# 3_6_1--esp32_-_7-30_-.net
KiCad netlist of a schematic drawn in EasyEDA Pro
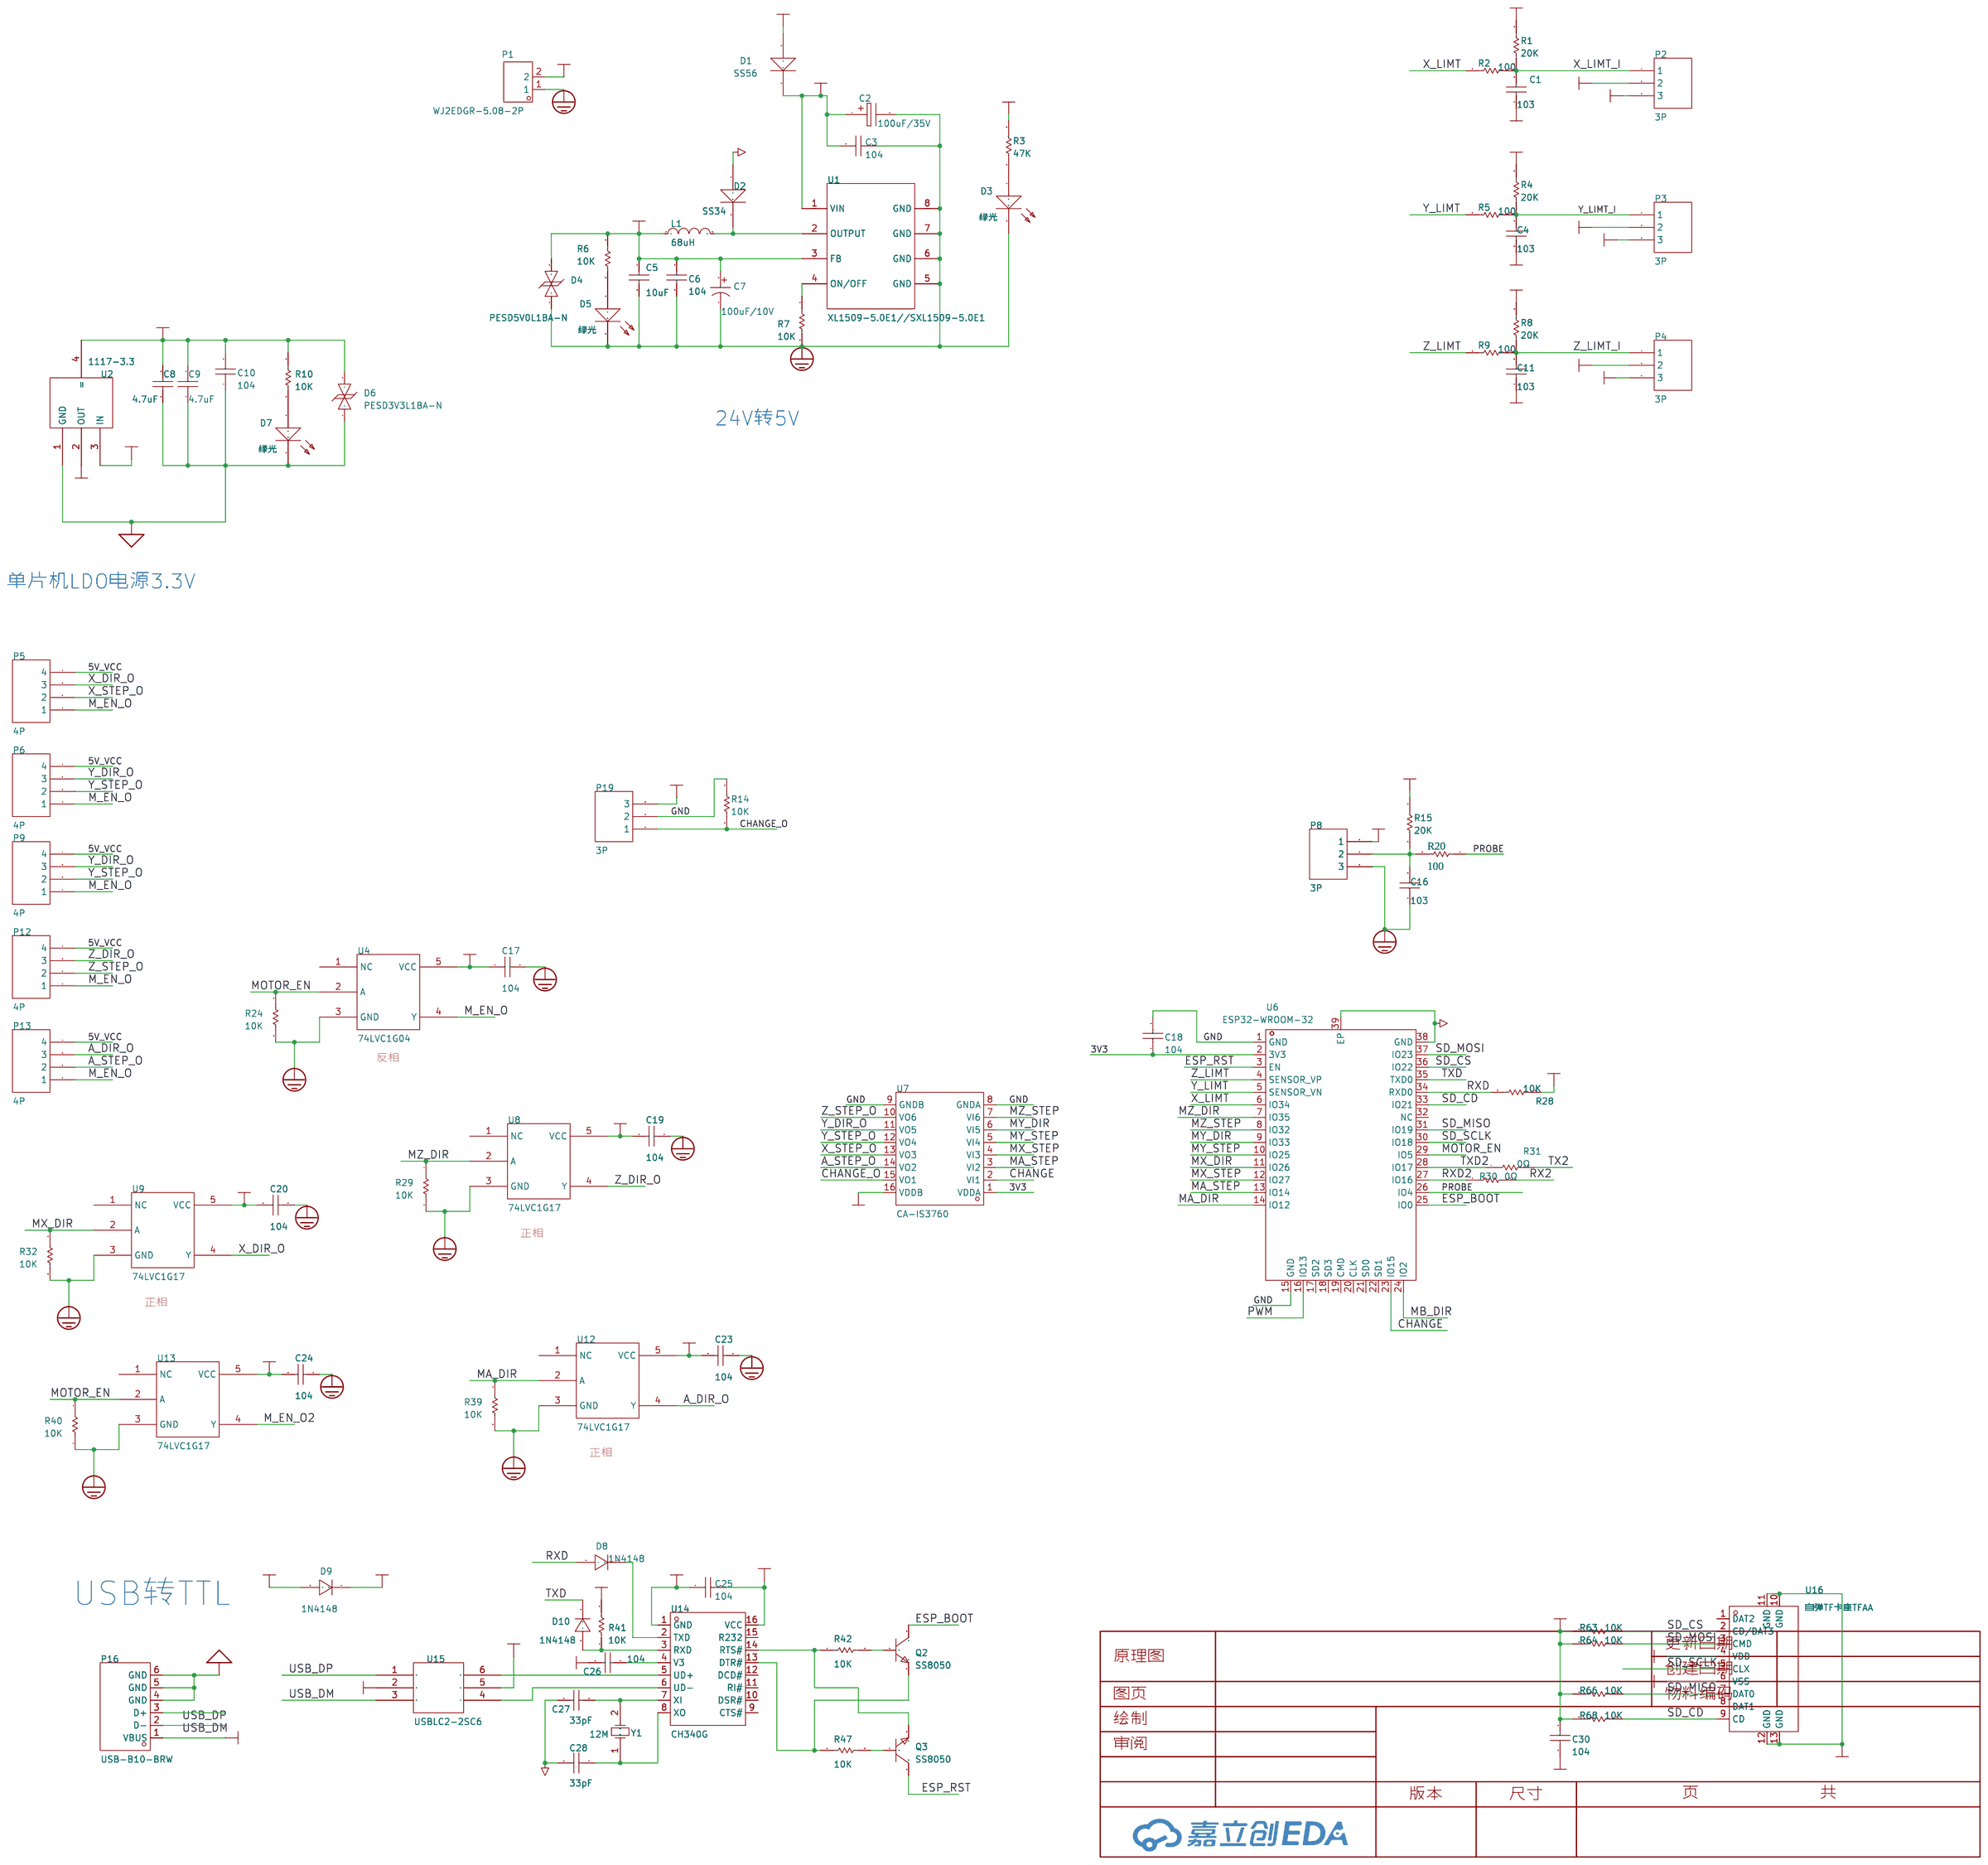
[diagram p0: schematic sheet]

(export (version "E")
  (design (tool "Eeschema 10.0.6"))
  (components
    (comp (ref "C1") (value "103") (footprint "easyedapro:11") (libsource (lib "easyedapro") (part "CAP")))
    (comp (ref "C2")
      (value "100uF/35V")
      (footprint "easyedapro:电解电容贴片10x10")
      (libsource (lib "easyedapro") (part "ELECTRO1"))
    )
    (comp (ref "C3")
      (value "104")
      (footprint "easyedapro:0603C")
      (description "Capacitor (Semiconductor SIM Model)")
      (libsource (lib "easyedapro") (part "Cap Semi"))
    )
    (comp (ref "C4") (value "103") (footprint "easyedapro:11") (libsource (lib "easyedapro") (part "CAP")))
    (comp (ref "C5") (value "10uF") (libsource (lib "") (part "CAP_1")))
    (comp (ref "C6")
      (value "104")
      (footprint "easyedapro:0603C")
      (description "Capacitor (Semiconductor SIM Model)")
      (libsource (lib "easyedapro") (part "Cap Semi"))
    )
    (comp (ref "C7")
      (value "100uF/10V")
      (footprint "easyedapro:CAP-SMD_BD5.0-L5.3-W5.3-RD")
      (fields (field (name "Manufacturer Part") "CS1A101M-CRD54") (field (name "Manufacturer") "ST(先科)"))
      (libsource (lib "easyedapro") (part "CS1A101M-CRD54"))
    )
    (comp (ref "C8") (value "4.7uF") (libsource (lib "") (part "CAP_1")))
    (comp (ref "C9") (value "4.7uF") (libsource (lib "") (part "CAP_1")))
    (comp (ref "C10")
      (value "104")
      (footprint "easyedapro:0603C")
      (description "Capacitor (Semiconductor SIM Model)")
      (libsource (lib "easyedapro") (part "Cap Semi"))
    )
    (comp (ref "C11") (value "103") (footprint "easyedapro:11") (libsource (lib "easyedapro") (part "CAP")))
    (comp (ref "C16") (value "103") (footprint "easyedapro:11") (libsource (lib "easyedapro") (part "CAP")))
    (comp (ref "C17")
      (value "104")
      (footprint "easyedapro:0603C")
      (description "Capacitor (Semiconductor SIM Model)")
      (libsource (lib "easyedapro") (part "Cap Semi"))
    )
    (comp (ref "C18")
      (value "104")
      (footprint "easyedapro:0603C")
      (description "Capacitor (Semiconductor SIM Model)")
      (libsource (lib "easyedapro") (part "Cap Semi"))
    )
    (comp (ref "C19")
      (value "104")
      (footprint "easyedapro:0603C")
      (description "Capacitor (Semiconductor SIM Model)")
      (libsource (lib "easyedapro") (part "Cap Semi"))
    )
    (comp (ref "C20")
      (value "104")
      (footprint "easyedapro:0603C")
      (description "Capacitor (Semiconductor SIM Model)")
      (libsource (lib "easyedapro") (part "Cap Semi"))
    )
    (comp (ref "C23")
      (value "104")
      (footprint "easyedapro:0603C")
      (description "Capacitor (Semiconductor SIM Model)")
      (libsource (lib "easyedapro") (part "Cap Semi"))
    )
    (comp (ref "C24")
      (value "104")
      (footprint "easyedapro:0603C")
      (description "Capacitor (Semiconductor SIM Model)")
      (libsource (lib "easyedapro") (part "Cap Semi"))
    )
    (comp (ref "C25")
      (value "104")
      (footprint "easyedapro:0603C")
      (description "Capacitor (Semiconductor SIM Model)")
      (libsource (lib "easyedapro") (part "Cap Semi"))
    )
    (comp (ref "C26")
      (value "104")
      (footprint "easyedapro:0603C")
      (description "Capacitor (Semiconductor SIM Model)")
      (libsource (lib "easyedapro") (part "Cap Semi"))
    )
    (comp (ref "C27")
      (value "18pF")
      (footprint "easyedapro:0603C")
      (description "Capacitor (Semiconductor SIM Model)")
      (libsource (lib "easyedapro") (part "Cap Semi"))
    )
    (comp (ref "C28")
      (value "18pF")
      (footprint "easyedapro:0603C")
      (description "Capacitor (Semiconductor SIM Model)")
      (libsource (lib "easyedapro") (part "Cap Semi"))
    )
    (comp (ref "C30")
      (value "104")
      (footprint "easyedapro:11")
      (description "Capacitor (Semiconductor SIM Model)")
      (libsource (lib "easyedapro") (part "Cap Semi"))
    )
    (comp (ref "D1") (value "SS56") (footprint "easyedapro:SMA") (libsource (lib "") (part "1N4148_1")))
    (comp (ref "D2") (value "SS34") (libsource (lib "easyedapro") (part "1N4148")))
    (comp (ref "D3")
      (value "绿光")
      (footprint "easyedapro:0603LED")
      (libsource (lib "easyedapro") (part "LED"))
    )
    (comp (ref "D4")
      (value "PESD5V0L1BA-N")
      (footprint "easyedapro:SOD-523_L1.2-W0.8-LS1.6-BI")
      (description "极性:Bidirectional;反向关断电压（典型值）:5V (Max);击穿电压（最小值）:6V;箝位电压:15V;峰值脉冲电流（10/1000us）:5A (8/20us);")
      (fields (field (name "Manufacturer") "BORN伯恩半导体"))
      (libsource (lib "easyedapro") (part "PESD5V0S1BBN"))
    )
    (comp (ref "D5")
      (value "绿光")
      (footprint "easyedapro:0603LED")
      (libsource (lib "easyedapro") (part "LED"))
    )
    (comp (ref "D6")
      (value "PESD3V3L1BA-N")
      (footprint "easyedapro:SOD-523_L1.2-W0.8-LS1.6-BI")
      (description "极性:Bidirectional;反向关断电压（典型值）:5V (Max);击穿电压（最小值）:6V;箝位电压:15V;峰值脉冲电流（10/1000us）:5A (8/20us);")
      (fields (field (name "Manufacturer") "BORN伯恩半导体"))
      (libsource (lib "easyedapro") (part "PESD5V0S1BBN"))
    )
    (comp (ref "D7")
      (value "绿光")
      (footprint "easyedapro:0603LED")
      (libsource (lib "easyedapro") (part "LED"))
    )
    (comp (ref "D8")
      (value "1N4148")
      (footprint "easyedapro:SOD-123_L2.8-W1.8-LS3.7-RD")
      (fields (field (name "Manufacturer") "MCC(美微科)"))
      (libsource (lib "easyedapro") (part "1N4148W-TP"))
    )
    (comp (ref "D9")
      (value "1N4148")
      (footprint "easyedapro:SOD-123_L2.8-W1.8-LS3.7-RD")
      (fields (field (name "Manufacturer") "MCC(美微科)"))
      (libsource (lib "easyedapro") (part "1N4148W-TP"))
    )
    (comp (ref "D10")
      (value "1N4148")
      (footprint "easyedapro:SOD-123_L2.8-W1.8-LS3.7-RD")
      (fields (field (name "Manufacturer") "MCC(美微科)"))
      (libsource (lib "easyedapro") (part "1N4148W-TP"))
    )
    (comp (ref "L1")
      (value "68uH")
      (footprint "easyedapro:IND-SMD_L7.0-W7.0_SMDRI74-330MT")
      (description "电感值:33uH;精度:±20%;额定电流:960mA;饱和电流(Isat):1.8A;类型:屏蔽电感;")
      (fields (field (name "Manufacturer Part") "SMDRI74-330MT") (field (name "Manufacturer") "SXN(顺翔诺)"))
      (libsource (lib "easyedapro") (part "SMDRI74-330MT"))
    )
    (comp (ref "P1")
      (value "WJ2EDGR-5.08-2P")
      (footprint "easyedapro:CONN-TH_WJ2EDGR-5.08-2P")
      (description "每排PIN数:2;安装方式:弯针;排数:1;间距:5.08mm;连接器类型:板端/插座-开口;")
      (fields (field (name "Manufacturer") "KANGNEX(康奈克斯电气)"))
      (libsource (lib "easyedapro") (part "WJ2EDGR-5.08-2P"))
    )
    (comp (ref "P2")
      (value "3P")
      (footprint "easyedapro:HDR1X3_CON")
      (libsource (lib "easyedapro") (part "3P"))
    )
    (comp (ref "P3")
      (value "3P")
      (footprint "easyedapro:HDR1X3_CON")
      (libsource (lib "easyedapro") (part "3P"))
    )
    (comp (ref "P4")
      (value "3P")
      (footprint "easyedapro:HDR1X3_CON")
      (libsource (lib "easyedapro") (part "3P"))
    )
    (comp (ref "P5")
      (value "4P")
      (footprint "easyedapro:HDR1X4_CON")
      (libsource (lib "easyedapro") (part "4P"))
    )
    (comp (ref "P6")
      (value "4P")
      (footprint "easyedapro:HDR1X4_CON")
      (libsource (lib "easyedapro") (part "4P"))
    )
    (comp (ref "P8")
      (value "3P")
      (footprint "easyedapro:HDR1X3_CON")
      (libsource (lib "easyedapro") (part "3P"))
    )
    (comp (ref "P9")
      (value "4P")
      (footprint "easyedapro:HDR1X4_CON")
      (libsource (lib "easyedapro") (part "4P"))
    )
    (comp (ref "P12")
      (value "4P")
      (footprint "easyedapro:HDR1X4_CON")
      (libsource (lib "easyedapro") (part "4P"))
    )
    (comp (ref "P13")
      (value "4P")
      (footprint "easyedapro:HDR1X4_CON")
      (libsource (lib "easyedapro") (part "4P"))
    )
    (comp (ref "P16")
      (value "USB-B10-BRW")
      (footprint "easyedapro:USB-B-TH_USB-B10-BRW")
      (fields (field (name "Manufacturer") "XUNPU(讯普)"))
      (libsource (lib "easyedapro") (part "USB-B10-BRW"))
    )
    (comp (ref "P19")
      (value "3P")
      (footprint "easyedapro:HDR1X3_CON")
      (libsource (lib "easyedapro") (part "3P"))
    )
    (comp (ref "Q2")
      (value "SS8050")
      (footprint "easyedapro:SOT-23-3_L2.9-W1.3-P1.90-LS2.4-BR")
      (fields (field (name "Manufacturer") "Doeshare(德芯)"))
      (libsource (lib "easyedapro") (part "SS8050_C2931717"))
    )
    (comp (ref "Q3")
      (value "SS8050")
      (footprint "easyedapro:SOT-23-3_L2.9-W1.3-P1.90-LS2.4-BR")
      (fields (field (name "Manufacturer") "Doeshare(德芯)"))
      (libsource (lib "easyedapro") (part "SS8050_C2931717"))
    )
    (comp (ref "R1")
      (value "20K")
      (footprint "easyedapro:10")
      (description "Resistor")
      (libsource (lib "") (part "RES_1"))
    )
    (comp (ref "R2")
      (value "100")
      (footprint "easyedapro:10")
      (description "Resistor")
      (libsource (lib "") (part "RES_1"))
    )
    (comp (ref "R3")
      (value "47K")
      (footprint "easyedapro:0603R")
      (description "Resistor")
      (libsource (lib "") (part "RES_1"))
    )
    (comp (ref "R4")
      (value "20K")
      (footprint "easyedapro:10")
      (description "Resistor")
      (libsource (lib "") (part "RES_1"))
    )
    (comp (ref "R5")
      (value "100")
      (footprint "easyedapro:10")
      (description "Resistor")
      (libsource (lib "") (part "RES_1"))
    )
    (comp (ref "R6")
      (value "10K")
      (footprint "easyedapro:0603R")
      (description "Resistor")
      (libsource (lib "") (part "RES_1"))
    )
    (comp (ref "R7")
      (value "10K")
      (footprint "easyedapro:0603R")
      (description "Resistor")
      (libsource (lib "") (part "RES_1"))
    )
    (comp (ref "R8")
      (value "20K")
      (footprint "easyedapro:10")
      (description "Resistor")
      (libsource (lib "") (part "RES_1"))
    )
    (comp (ref "R9")
      (value "100")
      (footprint "easyedapro:10")
      (description "Resistor")
      (libsource (lib "") (part "RES_1"))
    )
    (comp (ref "R10")
      (value "10K")
      (footprint "easyedapro:0603R")
      (description "Resistor")
      (libsource (lib "") (part "RES_1"))
    )
    (comp (ref "R14")
      (value "10K")
      (footprint "easyedapro:0603R")
      (description "Resistor")
      (libsource (lib "") (part "RES_1"))
    )
    (comp (ref "R15")
      (value "10K")
      (footprint "easyedapro:0603R")
      (description "Resistor")
      (libsource (lib "") (part "RES_1"))
    )
    (comp (ref "R20")
      (value "100")
      (description "Resistor")
      (fields (field (name "Publisher") "Altium Limited"))
      (libsource (lib "easyedapro") (part "RES"))
    )
    (comp (ref "R24")
      (value "10K")
      (description "Resistor")
      (fields (field (name "Publisher") "Altium Limited"))
      (libsource (lib "easyedapro") (part "RES"))
    )
    (comp (ref "R28")
      (value "10K")
      (footprint "easyedapro:0603R")
      (description "Resistor")
      (libsource (lib "") (part "RES_1"))
    )
    (comp (ref "R29")
      (value "10K")
      (description "Resistor")
      (fields (field (name "Publisher") "Altium Limited"))
      (libsource (lib "easyedapro") (part "RES"))
    )
    (comp (ref "R30")
      (value "0Ω")
      (description "Resistor")
      (fields (field (name "Publisher") "Altium Limited"))
      (libsource (lib "easyedapro") (part "RES"))
    )
    (comp (ref "R31")
      (value "0Ω")
      (description "Resistor")
      (fields (field (name "Publisher") "Altium Limited"))
      (libsource (lib "easyedapro") (part "RES"))
    )
    (comp (ref "R32")
      (value "10K")
      (description "Resistor")
      (fields (field (name "Publisher") "Altium Limited"))
      (libsource (lib "easyedapro") (part "RES"))
    )
    (comp (ref "R39")
      (value "10K")
      (description "Resistor")
      (fields (field (name "Publisher") "Altium Limited"))
      (libsource (lib "easyedapro") (part "RES"))
    )
    (comp (ref "R40")
      (value "10K")
      (description "Resistor")
      (fields (field (name "Publisher") "Altium Limited"))
      (libsource (lib "easyedapro") (part "RES"))
    )
    (comp (ref "R41")
      (value "10K")
      (footprint "easyedapro:0603R")
      (description "Resistor")
      (libsource (lib "") (part "RES_1"))
    )
    (comp (ref "R42")
      (value "10K")
      (footprint "easyedapro:0603R")
      (description "Resistor")
      (libsource (lib "") (part "RES_1"))
    )
    (comp (ref "R47")
      (value "10K")
      (footprint "easyedapro:0603R")
      (description "Resistor")
      (libsource (lib "") (part "RES_1"))
    )
    (comp (ref "R63")
      (value "10K")
      (footprint "easyedapro:10")
      (description "Resistor")
      (libsource (lib "") (part "RES_1"))
    )
    (comp (ref "R64")
      (value "10K")
      (footprint "easyedapro:10")
      (description "Resistor")
      (libsource (lib "") (part "RES_1"))
    )
    (comp (ref "R66")
      (value "10K")
      (footprint "easyedapro:10")
      (description "Resistor")
      (libsource (lib "") (part "RES_1"))
    )
    (comp (ref "R68")
      (value "10K")
      (footprint "easyedapro:10")
      (description "Resistor")
      (libsource (lib "") (part "RES_1"))
    )
    (comp (ref "U1")
      (value "XL1509-5.0E1//SXL1509-5.0E1")
      (footprint "easyedapro:SOIC-8_L5.0-W4.0-P1.27-LS6.0-BL")
      (description "功能类型:降压型;同步整流:-;输出通道数:-;拓扑结构:-;输入电压:-;输出电流(最大值):-;开关频率:-;")
      (fields (field (name "Manufacturer") "XLSEMI(芯龙)"))
      (libsource (lib "easyedapro") (part "XL1509-5.0E1"))
    )
    (comp (ref "U2")
      (value "1117-3.3")
      (footprint "easyedapro:SOT-223")
      (libsource (lib "easyedapro") (part "LM1117"))
    )
    (comp (ref "U4")
      (value "74LVC1G04")
      (footprint "easyedapro:SMD8")
      (libsource (lib "easyedapro") (part "74LVC1G04"))
    )
    (comp (ref "U6")
      (value "ESP32-WROOM-32")
      (footprint "easyedapro:WIFIM-SMD_ESP-WROOM-32")
      (description "WiFi+双模蓝牙 双核CPU 网口 顶配MCU 低功耗蓝牙 ESP32系列ESP-WROOM-32模组/ESP-32S 4MB")
      (fields (field (name "Manufacturer") "ESPRESSIF(乐鑫)"))
      (libsource (lib "easyedapro") (part "ESP-WROOM-32"))
    )
    (comp (ref "U7")
      (value "CA-IS3760")
      (footprint "easyedapro:SOIC-16_L9.9-W3.9-P1.27-LS6.0-BL")
      (fields (field (name "Manufacturer") "Chipanalog(川土微)"))
      (libsource (lib "easyedapro") (part "CA-IS3760HN"))
    )
    (comp (ref "U8")
      (value "74LVC1G17")
      (footprint "easyedapro:SMD8")
      (libsource (lib "easyedapro") (part "74LVC1G04"))
    )
    (comp (ref "U9")
      (value "74LVC1G17")
      (footprint "easyedapro:SMD8")
      (libsource (lib "easyedapro") (part "74LVC1G04"))
    )
    (comp (ref "U12")
      (value "74LVC1G17")
      (footprint "easyedapro:SMD8")
      (libsource (lib "easyedapro") (part "74LVC1G04"))
    )
    (comp (ref "U13")
      (value "74LVC1G17")
      (footprint "easyedapro:SMD8")
      (libsource (lib "easyedapro") (part "74LVC1G04"))
    )
    (comp (ref "U14")
      (value "CH340G")
      (footprint "easyedapro:SOIC-16_L9.9-W3.9-P1.27-LS6.0-BL")
      (description "应用功能:收发器;接口协议:USB 2.0;数据速率:2Mbps;")
      (fields (field (name "Manufacturer") "WCH(南京沁恒)"))
      (libsource (lib "easyedapro") (part "CH340G"))
    )
    (comp (ref "U15")
      (value "USBLC2-2SC6")
      (footprint "easyedapro:SOT-23-6")
      (libsource (lib "easyedapro") (part "DIP6"))
    )
    (comp (ref "U16")
      (value "自弹TF卡座TFAA")
      (footprint "easyedapro:SIM-SMD_C9900015645")
      (libsource (lib "easyedapro") (part "自弹TF卡座TFAA"))
    )
    (comp (ref "Y1")
      (value "12M")
      (footprint "easyedapro:晶振贴片49SSMD")
      (description "Crystal Oscillator")
      (libsource (lib "easyedapro") (part "XTAL"))
    )
  )
  (nets
    (net (code "1") (name "/A_DIR_O") (class "Default")
      (node (ref "P13") (pin "3") (pinfunction "3_3") (pintype "unspecified"))
      (node (ref "U12") (pin "4") (pinfunction "Y_4") (pintype "unspecified"))
    )
    (net (code "2") (name "/A_STEP_O") (class "Default")
      (node (ref "P13") (pin "2") (pinfunction "2_2") (pintype "unspecified"))
      (node (ref "U7") (pin "14") (pinfunction "VO2_14") (pintype "unspecified"))
    )
    (net (code "3") (name "/CHANGE") (class "Default")
      (node (ref "U6") (pin "23") (pinfunction "IO15_23") (pintype "unspecified"))
      (node (ref "U7") (pin "2") (pinfunction "VI1_2") (pintype "unspecified"))
    )
    (net (code "4") (name "/CHANGE_O") (class "Default")
      (node (ref "P19") (pin "1") (pinfunction "1_1") (pintype "unspecified"))
      (node (ref "R14") (pin "2") (pinfunction "2_2") (pintype "unspecified"))
      (node (ref "U7") (pin "15") (pinfunction "VO1_15") (pintype "unspecified"))
    )
    (net (code "5") (name "/ESP_BOOT") (class "Default")
      (node (ref "Q2") (pin "3") (pinfunction "C_3") (pintype "unspecified"))
      (node (ref "U6") (pin "25") (pinfunction "IO0_25") (pintype "unspecified"))
    )
    (net (code "6") (name "/ESP_RST") (class "Default")
      (node (ref "Q3") (pin "3") (pinfunction "C_3") (pintype "unspecified"))
      (node (ref "U6") (pin "3") (pinfunction "EN_3") (pintype "unspecified"))
    )
    (net (code "7") (name "/MA_DIR") (class "Default")
      (node (ref "R39") (pin "1") (pinfunction "1_1") (pintype "input"))
      (node (ref "U12") (pin "2") (pinfunction "A_2") (pintype "unspecified"))
      (node (ref "U6") (pin "14") (pinfunction "IO12_14") (pintype "unspecified"))
    )
    (net (code "8") (name "/MA_STEP") (class "Default")
      (node (ref "U6") (pin "13") (pinfunction "IO14_13") (pintype "unspecified"))
      (node (ref "U7") (pin "3") (pinfunction "VI2_3") (pintype "unspecified"))
    )
    (net (code "9") (name "/MB_DIR") (class "Default")
      (node (ref "U6") (pin "24") (pinfunction "IO2_24") (pintype "unspecified"))
    )
    (net (code "10") (name "/MOTOR_EN") (class "Default")
      (node (ref "R24") (pin "1") (pinfunction "1_1") (pintype "input"))
      (node (ref "R40") (pin "1") (pinfunction "1_1") (pintype "input"))
      (node (ref "U13") (pin "2") (pinfunction "A_2") (pintype "unspecified"))
      (node (ref "U4") (pin "2") (pinfunction "A_2") (pintype "unspecified"))
      (node (ref "U6") (pin "29") (pinfunction "IO5_29") (pintype "unspecified"))
    )
    (net (code "11") (name "/MX_DIR") (class "Default")
      (node (ref "R32") (pin "1") (pinfunction "1_1") (pintype "input"))
      (node (ref "U6") (pin "11") (pinfunction "IO26_11") (pintype "unspecified"))
      (node (ref "U9") (pin "2") (pinfunction "A_2") (pintype "unspecified"))
    )
    (net (code "12") (name "/MX_STEP") (class "Default")
      (node (ref "U6") (pin "12") (pinfunction "IO27_12") (pintype "unspecified"))
      (node (ref "U7") (pin "4") (pinfunction "VI3_4") (pintype "unspecified"))
    )
    (net (code "13") (name "/MY_DIR") (class "Default")
      (node (ref "U6") (pin "9") (pinfunction "IO33_9") (pintype "unspecified"))
      (node (ref "U7") (pin "6") (pinfunction "VI5_6") (pintype "unspecified"))
    )
    (net (code "14") (name "/MY_STEP") (class "Default")
      (node (ref "U6") (pin "10") (pinfunction "IO25_10") (pintype "unspecified"))
      (node (ref "U7") (pin "5") (pinfunction "VI4_5") (pintype "unspecified"))
    )
    (net (code "15") (name "/MZ_DIR") (class "Default")
      (node (ref "R29") (pin "1") (pinfunction "1_1") (pintype "input"))
      (node (ref "U6") (pin "7") (pinfunction "IO35_7") (pintype "unspecified"))
      (node (ref "U8") (pin "2") (pinfunction "A_2") (pintype "unspecified"))
    )
    (net (code "16") (name "/MZ_STEP") (class "Default")
      (node (ref "U6") (pin "8") (pinfunction "IO32_8") (pintype "unspecified"))
      (node (ref "U7") (pin "7") (pinfunction "VI6_7") (pintype "unspecified"))
    )
    (net (code "17") (name "/M_EN_O") (class "Default")
      (node (ref "P12") (pin "1") (pinfunction "1_1") (pintype "unspecified"))
      (node (ref "P13") (pin "1") (pinfunction "1_1") (pintype "unspecified"))
      (node (ref "P5") (pin "1") (pinfunction "1_1") (pintype "unspecified"))
      (node (ref "P6") (pin "1") (pinfunction "1_1") (pintype "unspecified"))
      (node (ref "P9") (pin "1") (pinfunction "1_1") (pintype "unspecified"))
      (node (ref "U4") (pin "4") (pinfunction "Y_4") (pintype "unspecified"))
    )
    (net (code "18") (name "/M_EN_O2") (class "Default")
      (node (ref "U13") (pin "4") (pinfunction "Y_4") (pintype "unspecified"))
    )
    (net (code "19") (name "/PROBE") (class "Default")
      (node (ref "R20") (pin "1") (pinfunction "1_1") (pintype "input"))
      (node (ref "U6") (pin "26") (pinfunction "IO4_26") (pintype "unspecified"))
    )
    (net (code "20") (name "/PWM") (class "Default")
      (node (ref "U6") (pin "16") (pinfunction "IO13_16") (pintype "unspecified"))
    )
    (net (code "21") (name "/RX2") (class "Default")
      (node (ref "R30") (pin "2") (pinfunction "2_2") (pintype "input"))
    )
    (net (code "22") (name "/RXD") (class "Default")
      (node (ref "D8") (pin "2") (pinfunction "A_2") (pintype "input"))
      (node (ref "R28") (pin "2") (pinfunction "2_2") (pintype "unspecified"))
      (node (ref "U6") (pin "34") (pinfunction "RXD0_34") (pintype "unspecified"))
    )
    (net (code "23") (name "/RXD2") (class "Default")
      (node (ref "R30") (pin "1") (pinfunction "1_1") (pintype "input"))
      (node (ref "U6") (pin "27") (pinfunction "IO16_27") (pintype "unspecified"))
    )
    (net (code "24") (name "/SD_CD") (class "Default")
      (node (ref "R68") (pin "1") (pinfunction "1_1") (pintype "unspecified"))
      (node (ref "U16") (pin "9") (pinfunction "CD_9") (pintype "unspecified"))
      (node (ref "U6") (pin "33") (pinfunction "IO21_33") (pintype "unspecified"))
    )
    (net (code "25") (name "/SD_CS") (class "Default")
      (node (ref "R63") (pin "1") (pinfunction "1_1") (pintype "unspecified"))
      (node (ref "U16") (pin "2") (pinfunction "CD/DAT3_2") (pintype "unspecified"))
      (node (ref "U6") (pin "36") (pinfunction "IO22_36") (pintype "unspecified"))
    )
    (net (code "26") (name "/SD_MISO") (class "Default")
      (node (ref "R66") (pin "1") (pinfunction "1_1") (pintype "unspecified"))
      (node (ref "U16") (pin "7") (pinfunction "DAT0_7") (pintype "unspecified"))
      (node (ref "U6") (pin "31") (pinfunction "IO19_31") (pintype "unspecified"))
    )
    (net (code "27") (name "/SD_MOSI") (class "Default")
      (node (ref "R64") (pin "1") (pinfunction "1_1") (pintype "unspecified"))
      (node (ref "U16") (pin "3") (pinfunction "CMD_3") (pintype "unspecified"))
      (node (ref "U6") (pin "37") (pinfunction "IO23_37") (pintype "unspecified"))
    )
    (net (code "28") (name "/SD_SCLK") (class "Default")
      (node (ref "U16") (pin "5") (pinfunction "CLX_5") (pintype "unspecified"))
      (node (ref "U6") (pin "30") (pinfunction "IO18_30") (pintype "unspecified"))
    )
    (net (code "29") (name "/TX2") (class "Default")
      (node (ref "R31") (pin "2") (pinfunction "2_2") (pintype "input"))
    )
    (net (code "30") (name "/TXD") (class "Default")
      (node (ref "D10") (pin "1") (pinfunction "c_1") (pintype "input"))
      (node (ref "U6") (pin "35") (pinfunction "TXD0_35") (pintype "unspecified"))
    )
    (net (code "31") (name "/TXD2") (class "Default")
      (node (ref "R31") (pin "1") (pinfunction "1_1") (pintype "input"))
      (node (ref "U6") (pin "28") (pinfunction "IO17_28") (pintype "unspecified"))
    )
    (net (code "32") (name "/USB_DM") (class "Default")
      (node (ref "P16") (pin "2") (pinfunction "D-_2") (pintype "unspecified"))
      (node (ref "U15") (pin "3") (pinfunction "3_3") (pintype "unspecified"))
    )
    (net (code "33") (name "/USB_DP") (class "Default")
      (node (ref "P16") (pin "3") (pinfunction "D+_3") (pintype "unspecified"))
      (node (ref "U15") (pin "1") (pinfunction "1_1") (pintype "unspecified"))
    )
    (net (code "34") (name "/X_DIR_O") (class "Default")
      (node (ref "P5") (pin "3") (pinfunction "3_3") (pintype "unspecified"))
      (node (ref "U9") (pin "4") (pinfunction "Y_4") (pintype "unspecified"))
    )
    (net (code "35") (name "/X_LIMT") (class "Default")
      (node (ref "R2") (pin "2") (pinfunction "2_2") (pintype "unspecified"))
      (node (ref "U6") (pin "6") (pinfunction "IO34_6") (pintype "unspecified"))
    )
    (net (code "36") (name "/X_LIMT_I") (class "Default")
      (node (ref "C1") (pin "2") (pinfunction "2_2") (pintype "unspecified"))
      (node (ref "P2") (pin "1") (pinfunction "1_1") (pintype "unspecified"))
      (node (ref "R1") (pin "1") (pinfunction "1_1") (pintype "unspecified"))
      (node (ref "R2") (pin "1") (pinfunction "1_1") (pintype "unspecified"))
    )
    (net (code "37") (name "/X_STEP_O") (class "Default")
      (node (ref "P5") (pin "2") (pinfunction "2_2") (pintype "unspecified"))
      (node (ref "U7") (pin "13") (pinfunction "VO3_13") (pintype "unspecified"))
    )
    (net (code "38") (name "/Y_DIR_O") (class "Default")
      (node (ref "P6") (pin "3") (pinfunction "3_3") (pintype "unspecified"))
      (node (ref "P9") (pin "3") (pinfunction "3_3") (pintype "unspecified"))
      (node (ref "U7") (pin "11") (pinfunction "VO5_11") (pintype "unspecified"))
    )
    (net (code "39") (name "/Y_LIMT") (class "Default")
      (node (ref "R5") (pin "2") (pinfunction "2_2") (pintype "unspecified"))
      (node (ref "U6") (pin "5") (pinfunction "SENSOR_VN_5") (pintype "unspecified"))
    )
    (net (code "40") (name "/Y_LIMT_I") (class "Default")
      (node (ref "C4") (pin "2") (pinfunction "2_2") (pintype "unspecified"))
      (node (ref "P3") (pin "1") (pinfunction "1_1") (pintype "unspecified"))
      (node (ref "R4") (pin "1") (pinfunction "1_1") (pintype "unspecified"))
      (node (ref "R5") (pin "1") (pinfunction "1_1") (pintype "unspecified"))
    )
    (net (code "41") (name "/Y_STEP_O") (class "Default")
      (node (ref "P6") (pin "2") (pinfunction "2_2") (pintype "unspecified"))
      (node (ref "P9") (pin "2") (pinfunction "2_2") (pintype "unspecified"))
      (node (ref "U7") (pin "12") (pinfunction "VO4_12") (pintype "unspecified"))
    )
    (net (code "42") (name "/Z_DIR_O") (class "Default")
      (node (ref "P12") (pin "3") (pinfunction "3_3") (pintype "unspecified"))
      (node (ref "U8") (pin "4") (pinfunction "Y_4") (pintype "unspecified"))
    )
    (net (code "43") (name "/Z_LIMT") (class "Default")
      (node (ref "R9") (pin "2") (pinfunction "2_2") (pintype "unspecified"))
      (node (ref "U6") (pin "4") (pinfunction "SENSOR_VP_4") (pintype "unspecified"))
    )
    (net (code "44") (name "/Z_LIMT_I") (class "Default")
      (node (ref "C11") (pin "2") (pinfunction "2_2") (pintype "unspecified"))
      (node (ref "P4") (pin "1") (pinfunction "1_1") (pintype "unspecified"))
      (node (ref "R8") (pin "1") (pinfunction "1_1") (pintype "unspecified"))
      (node (ref "R9") (pin "1") (pinfunction "1_1") (pintype "unspecified"))
    )
    (net (code "45") (name "/Z_STEP_O") (class "Default")
      (node (ref "P12") (pin "2") (pinfunction "2_2") (pintype "unspecified"))
      (node (ref "U7") (pin "10") (pinfunction "VO6_10") (pintype "unspecified"))
    )
    (net (code "46") (name "3V3") (class "Default")
      (node (ref "C10") (pin "2") (pinfunction "2_2") (pintype "unspecified"))
      (node (ref "C18") (pin "1") (pinfunction "1_1") (pintype "unspecified"))
      (node (ref "C30") (pin "2") (pinfunction "2_2") (pintype "unspecified"))
      (node (ref "C8") (pin "2") (pinfunction "2_2") (pintype "input"))
      (node (ref "C9") (pin "2") (pinfunction "2_2") (pintype "input"))
      (node (ref "D6") (pin "2") (pinfunction "2_2") (pintype "input"))
      (node (ref "R10") (pin "2") (pinfunction "2_2") (pintype "unspecified"))
      (node (ref "R28") (pin "1") (pinfunction "1_1") (pintype "unspecified"))
      (node (ref "R63") (pin "2") (pinfunction "2_2") (pintype "unspecified"))
      (node (ref "R64") (pin "2") (pinfunction "2_2") (pintype "unspecified"))
      (node (ref "R66") (pin "2") (pinfunction "2_2") (pintype "unspecified"))
      (node (ref "R68") (pin "2") (pinfunction "2_2") (pintype "unspecified"))
      (node (ref "U16") (pin "4") (pinfunction "VDD_4") (pintype "unspecified"))
      (node (ref "U2") (pin "2") (pinfunction "OUT_2") (pintype "unspecified"))
      (node (ref "U2") (pin "4") (pinfunction "=_4") (pintype "unspecified"))
      (node (ref "U6") (pin "2") (pinfunction "3V3_2") (pintype "unspecified"))
      (node (ref "U7") (pin "1") (pinfunction "VDDA_1") (pintype "unspecified"))
    )
    (net (code "47") (name "5V_VCC") (class "Default")
      (node (ref "C17") (pin "2") (pinfunction "2_2") (pintype "unspecified"))
      (node (ref "C19") (pin "2") (pinfunction "2_2") (pintype "unspecified"))
      (node (ref "C20") (pin "2") (pinfunction "2_2") (pintype "unspecified"))
      (node (ref "C23") (pin "2") (pinfunction "2_2") (pintype "unspecified"))
      (node (ref "C24") (pin "2") (pinfunction "2_2") (pintype "unspecified"))
      (node (ref "C25") (pin "1") (pinfunction "1_1") (pintype "unspecified"))
      (node (ref "C5") (pin "1") (pinfunction "1_1") (pintype "input"))
      (node (ref "C6") (pin "2") (pinfunction "2_2") (pintype "unspecified"))
      (node (ref "C7") (pin "1") (pinfunction "1_1") (pintype "input"))
      (node (ref "D4") (pin "2") (pinfunction "2_2") (pintype "input"))
      (node (ref "D9") (pin "1") (pinfunction "c_1") (pintype "input"))
      (node (ref "L1") (pin "1") (pinfunction "1_1") (pintype "unspecified"))
      (node (ref "P12") (pin "4") (pinfunction "4_4") (pintype "unspecified"))
      (node (ref "P13") (pin "4") (pinfunction "4_4") (pintype "unspecified"))
      (node (ref "P19") (pin "3") (pinfunction "3_3") (pintype "unspecified"))
      (node (ref "P2") (pin "3") (pinfunction "3_3") (pintype "unspecified"))
      (node (ref "P3") (pin "3") (pinfunction "3_3") (pintype "unspecified"))
      (node (ref "P4") (pin "3") (pinfunction "3_3") (pintype "unspecified"))
      (node (ref "P5") (pin "4") (pinfunction "4_4") (pintype "unspecified"))
      (node (ref "P6") (pin "4") (pinfunction "4_4") (pintype "unspecified"))
      (node (ref "P8") (pin "1") (pinfunction "1_1") (pintype "unspecified"))
      (node (ref "P9") (pin "4") (pinfunction "4_4") (pintype "unspecified"))
      (node (ref "R1") (pin "2") (pinfunction "2_2") (pintype "unspecified"))
      (node (ref "R15") (pin "1") (pinfunction "1_1") (pintype "unspecified"))
      (node (ref "R4") (pin "2") (pinfunction "2_2") (pintype "unspecified"))
      (node (ref "R41") (pin "2") (pinfunction "2_2") (pintype "unspecified"))
      (node (ref "R6") (pin "2") (pinfunction "2_2") (pintype "unspecified"))
      (node (ref "R8") (pin "2") (pinfunction "2_2") (pintype "unspecified"))
      (node (ref "U1") (pin "3") (pinfunction "FB_3") (pintype "input"))
      (node (ref "U12") (pin "5") (pinfunction "VCC_5") (pintype "unspecified"))
      (node (ref "U13") (pin "5") (pinfunction "VCC_5") (pintype "unspecified"))
      (node (ref "U14") (pin "16") (pinfunction "VCC_16") (pintype "unspecified"))
      (node (ref "U2") (pin "3") (pinfunction "IN_3") (pintype "unspecified"))
      (node (ref "U4") (pin "5") (pinfunction "VCC_5") (pintype "unspecified"))
      (node (ref "U7") (pin "16") (pinfunction "VDDB_16") (pintype "unspecified"))
      (node (ref "U8") (pin "5") (pinfunction "VCC_5") (pintype "unspecified"))
      (node (ref "U9") (pin "5") (pinfunction "VCC_5") (pintype "unspecified"))
    )
    (net (code "48") (name "24V") (class "Default")
      (node (ref "D1") (pin "1") (pinfunction "1_1") (pintype "unspecified"))
      (node (ref "P1") (pin "2") (pinfunction "2_2") (pintype "input"))
      (node (ref "R3") (pin "2") (pinfunction "2_2") (pintype "unspecified"))
    )
    (net (code "49") (name "GND") (class "Default")
      (node (ref "C1") (pin "1") (pinfunction "1_1") (pintype "unspecified"))
      (node (ref "C10") (pin "1") (pinfunction "1_1") (pintype "unspecified"))
      (node (ref "C11") (pin "1") (pinfunction "1_1") (pintype "unspecified"))
      (node (ref "C16") (pin "1") (pinfunction "1_1") (pintype "unspecified"))
      (node (ref "C17") (pin "1") (pinfunction "1_1") (pintype "unspecified"))
      (node (ref "C18") (pin "2") (pinfunction "2_2") (pintype "unspecified"))
      (node (ref "C19") (pin "1") (pinfunction "1_1") (pintype "unspecified"))
      (node (ref "C2") (pin "2") (pintype "unspecified"))
      (node (ref "C20") (pin "1") (pinfunction "1_1") (pintype "unspecified"))
      (node (ref "C23") (pin "1") (pinfunction "1_1") (pintype "unspecified"))
      (node (ref "C24") (pin "1") (pinfunction "1_1") (pintype "unspecified"))
      (node (ref "C25") (pin "2") (pinfunction "2_2") (pintype "unspecified"))
      (node (ref "C26") (pin "2") (pinfunction "2_2") (pintype "unspecified"))
      (node (ref "C27") (pin "2") (pinfunction "2_2") (pintype "unspecified"))
      (node (ref "C28") (pin "2") (pinfunction "2_2") (pintype "unspecified"))
      (node (ref "C3") (pin "1") (pinfunction "1_1") (pintype "unspecified"))
      (node (ref "C30") (pin "1") (pinfunction "1_1") (pintype "unspecified"))
      (node (ref "C4") (pin "1") (pinfunction "1_1") (pintype "unspecified"))
      (node (ref "C5") (pin "2") (pinfunction "2_2") (pintype "input"))
      (node (ref "C6") (pin "1") (pinfunction "1_1") (pintype "unspecified"))
      (node (ref "C7") (pin "2") (pinfunction "2_2") (pintype "input"))
      (node (ref "C8") (pin "1") (pinfunction "1_1") (pintype "input"))
      (node (ref "C9") (pin "1") (pinfunction "1_1") (pintype "input"))
      (node (ref "D2") (pin "1") (pinfunction "1_1") (pintype "input"))
      (node (ref "D3") (pin "2") (pinfunction "2_2") (pintype "unspecified"))
      (node (ref "D4") (pin "1") (pinfunction "1_1") (pintype "input"))
      (node (ref "D5") (pin "2") (pinfunction "2_2") (pintype "unspecified"))
      (node (ref "D6") (pin "1") (pinfunction "1_1") (pintype "input"))
      (node (ref "D7") (pin "2") (pinfunction "2_2") (pintype "unspecified"))
      (node (ref "P1") (pin "1") (pinfunction "1_1") (pintype "input"))
      (node (ref "P16") (pin "4") (pinfunction "GND_4") (pintype "unspecified"))
      (node (ref "P16") (pin "5") (pinfunction "GND_5") (pintype "unspecified"))
      (node (ref "P16") (pin "6") (pinfunction "GND_6") (pintype "unspecified"))
      (node (ref "P19") (pin "2") (pinfunction "2_2") (pintype "unspecified"))
      (node (ref "P2") (pin "2") (pinfunction "2_2") (pintype "unspecified"))
      (node (ref "P3") (pin "2") (pinfunction "2_2") (pintype "unspecified"))
      (node (ref "P4") (pin "2") (pinfunction "2_2") (pintype "unspecified"))
      (node (ref "P8") (pin "3") (pinfunction "3_3") (pintype "unspecified"))
      (node (ref "R14") (pin "1") (pinfunction "1_1") (pintype "unspecified"))
      (node (ref "R24") (pin "2") (pinfunction "2_2") (pintype "input"))
      (node (ref "R29") (pin "2") (pinfunction "2_2") (pintype "input"))
      (node (ref "R32") (pin "2") (pinfunction "2_2") (pintype "input"))
      (node (ref "R39") (pin "2") (pinfunction "2_2") (pintype "input"))
      (node (ref "R40") (pin "2") (pinfunction "2_2") (pintype "input"))
      (node (ref "R7") (pin "2") (pinfunction "2_2") (pintype "unspecified"))
      (node (ref "U1") (pin "5") (pinfunction "GND_5") (pintype "input"))
      (node (ref "U1") (pin "6") (pinfunction "GND_6") (pintype "input"))
      (node (ref "U1") (pin "7") (pinfunction "GND_7") (pintype "input"))
      (node (ref "U1") (pin "8") (pinfunction "GND_8") (pintype "input"))
      (node (ref "U12") (pin "3") (pinfunction "GND_3") (pintype "unspecified"))
      (node (ref "U13") (pin "3") (pinfunction "GND_3") (pintype "unspecified"))
      (node (ref "U14") (pin "1") (pinfunction "GND_1") (pintype "unspecified"))
      (node (ref "U15") (pin "2") (pinfunction "2_2") (pintype "unspecified"))
      (node (ref "U16") (pin "10") (pinfunction "GND_10") (pintype "unspecified"))
      (node (ref "U16") (pin "11") (pinfunction "GND_11") (pintype "unspecified"))
      (node (ref "U16") (pin "12") (pinfunction "GND_12") (pintype "unspecified"))
      (node (ref "U16") (pin "13") (pinfunction "GND_13") (pintype "unspecified"))
      (node (ref "U16") (pin "6") (pinfunction "VSS_6") (pintype "unspecified"))
      (node (ref "U2") (pin "1") (pinfunction "GND_1") (pintype "unspecified"))
      (node (ref "U4") (pin "3") (pinfunction "GND_3") (pintype "unspecified"))
      (node (ref "U6") (pin "1") (pinfunction "GND_1") (pintype "unspecified"))
      (node (ref "U6") (pin "15") (pinfunction "GND_15") (pintype "unspecified"))
      (node (ref "U6") (pin "38") (pinfunction "GND_38") (pintype "unspecified"))
      (node (ref "U6") (pin "39") (pinfunction "EP_39") (pintype "unspecified"))
      (node (ref "U7") (pin "8") (pinfunction "GNDA_8") (pintype "unspecified"))
      (node (ref "U7") (pin "9") (pinfunction "GNDB_9") (pintype "unspecified"))
      (node (ref "U8") (pin "3") (pinfunction "GND_3") (pintype "unspecified"))
      (node (ref "U9") (pin "3") (pinfunction "GND_3") (pintype "unspecified"))
    )
    (net (code "50") (name "Net-(C16-Pad2)") (class "Default")
      (node (ref "C16") (pin "2") (pinfunction "2_2") (pintype "unspecified"))
      (node (ref "P8") (pin "2") (pinfunction "2_2") (pintype "unspecified"))
      (node (ref "R15") (pin "2") (pinfunction "2_2") (pintype "unspecified"))
      (node (ref "R20") (pin "2") (pinfunction "2_2") (pintype "input"))
    )
    (net (code "51") (name "Net-(D3-Pad1)") (class "Default")
      (node (ref "D3") (pin "1") (pinfunction "1_1") (pintype "unspecified"))
      (node (ref "R3") (pin "1") (pinfunction "1_1") (pintype "unspecified"))
    )
    (net (code "52") (name "Net-(D5-Pad1)") (class "Default")
      (node (ref "D5") (pin "1") (pinfunction "1_1") (pintype "unspecified"))
      (node (ref "R6") (pin "1") (pinfunction "1_1") (pintype "unspecified"))
    )
    (net (code "53") (name "Net-(D7-Pad1)") (class "Default")
      (node (ref "D7") (pin "1") (pinfunction "1_1") (pintype "unspecified"))
      (node (ref "R10") (pin "1") (pinfunction "1_1") (pintype "unspecified"))
    )
    (net (code "54") (name "Net-(D8-c)") (class "Default")
      (node (ref "D8") (pin "1") (pinfunction "c_1") (pintype "input"))
      (node (ref "U14") (pin "2") (pinfunction "TXD_2") (pintype "unspecified"))
    )
    (net (code "55") (name "Net-(D10-A)") (class "Default")
      (node (ref "D10") (pin "2") (pinfunction "A_2") (pintype "input"))
      (node (ref "R41") (pin "1") (pinfunction "1_1") (pintype "unspecified"))
      (node (ref "U14") (pin "3") (pinfunction "RXD_3") (pintype "unspecified"))
    )
    (net (code "56") (name "Net-(Q2-B)") (class "Default")
      (node (ref "Q2") (pin "1") (pinfunction "B_1") (pintype "unspecified"))
      (node (ref "R42") (pin "2") (pinfunction "2_2") (pintype "unspecified"))
    )
    (net (code "57") (name "Net-(Q2-E)") (class "Default")
      (node (ref "Q2") (pin "2") (pinfunction "E_2") (pintype "unspecified"))
      (node (ref "R47") (pin "1") (pinfunction "1_1") (pintype "unspecified"))
      (node (ref "U14") (pin "13") (pinfunction "DTR#_13") (pintype "unspecified"))
    )
    (net (code "58") (name "Net-(Q3-B)") (class "Default")
      (node (ref "Q3") (pin "1") (pinfunction "B_1") (pintype "unspecified"))
      (node (ref "R47") (pin "2") (pinfunction "2_2") (pintype "unspecified"))
    )
    (net (code "59") (name "Net-(Q3-E)") (class "Default")
      (node (ref "Q3") (pin "2") (pinfunction "E_2") (pintype "unspecified"))
      (node (ref "R42") (pin "1") (pinfunction "1_1") (pintype "unspecified"))
      (node (ref "U14") (pin "14") (pinfunction "RTS#_14") (pintype "unspecified"))
    )
    (net (code "60") (name "Net-(U1-ON{slash}OFF)") (class "Default")
      (node (ref "R7") (pin "1") (pinfunction "1_1") (pintype "unspecified"))
      (node (ref "U1") (pin "4") (pinfunction "ON/OFF_4") (pintype "input"))
    )
    (net (code "61") (name "Net-(U1-OUTPUT)") (class "Default")
      (node (ref "D2") (pin "2") (pinfunction "2_2") (pintype "input"))
      (node (ref "L1") (pin "2") (pinfunction "2_2") (pintype "unspecified"))
      (node (ref "U1") (pin "2") (pinfunction "OUTPUT_2") (pintype "input"))
    )
    (net (code "62") (name "Net-(U14-UD+)") (class "Default")
      (node (ref "U14") (pin "5") (pinfunction "UD+_5") (pintype "unspecified"))
      (node (ref "U15") (pin "6") (pinfunction "6_6") (pintype "unspecified"))
    )
    (net (code "63") (name "Net-(U14-UD-)") (class "Default")
      (node (ref "U14") (pin "6") (pinfunction "UD-_6") (pintype "unspecified"))
      (node (ref "U15") (pin "4") (pinfunction "4_4") (pintype "unspecified"))
    )
    (net (code "64") (name "Net-(U14-V3)") (class "Default")
      (node (ref "C26") (pin "1") (pinfunction "1_1") (pintype "unspecified"))
      (node (ref "U14") (pin "4") (pinfunction "V3_4") (pintype "unspecified"))
    )
    (net (code "65") (name "Net-(U14-XI)") (class "Default")
      (node (ref "C27") (pin "1") (pinfunction "1_1") (pintype "unspecified"))
      (node (ref "U14") (pin "7") (pinfunction "XI_7") (pintype "unspecified"))
      (node (ref "Y1") (pin "2") (pinfunction "OSC2_2") (pintype "unspecified"))
    )
    (net (code "66") (name "Net-(U14-XO)") (class "Default")
      (node (ref "C28") (pin "1") (pinfunction "1_1") (pintype "unspecified"))
      (node (ref "U14") (pin "8") (pinfunction "XO_8") (pintype "unspecified"))
      (node (ref "Y1") (pin "1") (pinfunction "OSC1_1") (pintype "unspecified"))
    )
    (net (code "67") (name "VIN_24V") (class "Default")
      (node (ref "C2") (pin "1") (pintype "unspecified"))
      (node (ref "C3") (pin "2") (pinfunction "2_2") (pintype "unspecified"))
      (node (ref "D1") (pin "2") (pinfunction "2_2") (pintype "unspecified"))
      (node (ref "U1") (pin "1") (pinfunction "VIN_1") (pintype "input"))
    )
    (net (code "68") (name "VUSB") (class "Default")
      (node (ref "D9") (pin "2") (pinfunction "A_2") (pintype "input"))
      (node (ref "P16") (pin "1") (pinfunction "VBUS_1") (pintype "unspecified"))
      (node (ref "U15") (pin "5") (pinfunction "5_5") (pintype "unspecified"))
    )
    (net (code "69") (name "unconnected-(U4-NC-Pad1)") (class "Default")
      (node (ref "U4") (pin "1") (pinfunction "NC_1") (pintype "unspecified"))
    )
    (net (code "70") (name "unconnected-(U6-CLK-Pad20)") (class "Default")
      (node (ref "U6") (pin "20") (pinfunction "CLK_20") (pintype "unspecified"))
    )
    (net (code "71") (name "unconnected-(U6-CMD-Pad19)") (class "Default")
      (node (ref "U6") (pin "19") (pinfunction "CMD_19") (pintype "unspecified"))
    )
    (net (code "72") (name "unconnected-(U6-NC-Pad32)") (class "Default")
      (node (ref "U6") (pin "32") (pinfunction "NC_32") (pintype "unspecified"))
    )
    (net (code "73") (name "unconnected-(U6-SD0-Pad21)") (class "Default")
      (node (ref "U6") (pin "21") (pinfunction "SD0_21") (pintype "unspecified"))
    )
    (net (code "74") (name "unconnected-(U6-SD1-Pad22)") (class "Default")
      (node (ref "U6") (pin "22") (pinfunction "SD1_22") (pintype "unspecified"))
    )
    (net (code "75") (name "unconnected-(U6-SD2-Pad17)") (class "Default")
      (node (ref "U6") (pin "17") (pinfunction "SD2_17") (pintype "unspecified"))
    )
    (net (code "76") (name "unconnected-(U6-SD3-Pad18)") (class "Default")
      (node (ref "U6") (pin "18") (pinfunction "SD3_18") (pintype "unspecified"))
    )
    (net (code "77") (name "unconnected-(U8-NC-Pad1)") (class "Default")
      (node (ref "U8") (pin "1") (pinfunction "NC_1") (pintype "unspecified"))
    )
    (net (code "78") (name "unconnected-(U9-NC-Pad1)") (class "Default")
      (node (ref "U9") (pin "1") (pinfunction "NC_1") (pintype "unspecified"))
    )
    (net (code "79") (name "unconnected-(U12-NC-Pad1)") (class "Default")
      (node (ref "U12") (pin "1") (pinfunction "NC_1") (pintype "unspecified"))
    )
    (net (code "80") (name "unconnected-(U13-NC-Pad1)") (class "Default")
      (node (ref "U13") (pin "1") (pinfunction "NC_1") (pintype "unspecified"))
    )
    (net (code "81") (name "unconnected-(U14-CTS#-Pad9)") (class "Default")
      (node (ref "U14") (pin "9") (pinfunction "CTS#_9") (pintype "unspecified"))
    )
    (net (code "82") (name "unconnected-(U14-DCD#-Pad12)") (class "Default")
      (node (ref "U14") (pin "12") (pinfunction "DCD#_12") (pintype "unspecified"))
    )
    (net (code "83") (name "unconnected-(U14-DSR#-Pad10)") (class "Default")
      (node (ref "U14") (pin "10") (pinfunction "DSR#_10") (pintype "unspecified"))
    )
    (net (code "84") (name "unconnected-(U14-R232-Pad15)") (class "Default")
      (node (ref "U14") (pin "15") (pinfunction "R232_15") (pintype "unspecified"))
    )
    (net (code "85") (name "unconnected-(U14-RI#-Pad11)") (class "Default")
      (node (ref "U14") (pin "11") (pinfunction "RI#_11") (pintype "unspecified"))
    )
    (net (code "86") (name "unconnected-(U16-DAT1-Pad8)") (class "Default")
      (node (ref "U16") (pin "8") (pinfunction "DAT1_8") (pintype "unspecified"))
    )
    (net (code "87") (name "unconnected-(U16-DAT2-Pad1)") (class "Default")
      (node (ref "U16") (pin "1") (pinfunction "DAT2_1") (pintype "unspecified"))
    )
  )
)
